# RELAY_8CH.net
KiCad netlist of a schematic drawn in Altium Designer
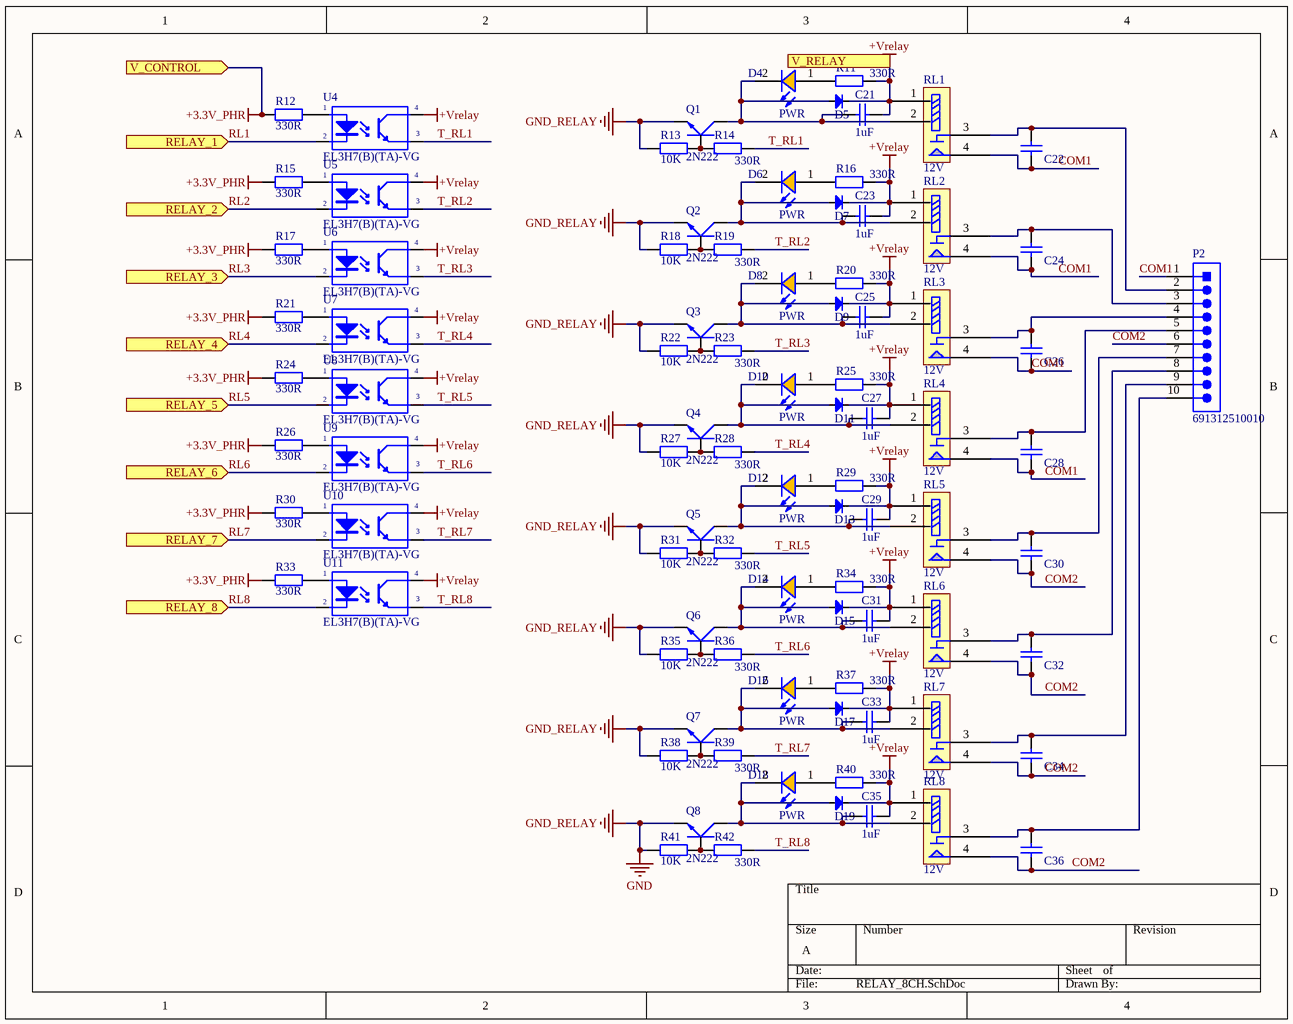
[diagram p0: RELAY_8CH.SchDoc]

(export (version "E")
  (design (tool "Eeschema 10.0.6"))
  (components
    (comp (ref "C21")
      (value "1uF")
      (footprint "CAP_0805")
      (description "WCAP-CSGP General Purpose Ceramic Capacitors")
      (fields (field (name "PART NUMBER") "885012005001") (field (name "PUBLISHER") "Wurth Elektronik"))
      (libsource (lib "ThanhNhan") (part "CAP_SMD"))
    )
    (comp (ref "C22")
      (value "R82DC3100DQ50J")
      (footprint "CAP FILM 5mm")
      (fields (field (name "MOUSER PART NUMBER") "80-R82DC3100DQ50J"))
      (libsource (lib "ThanhNhan") (part "CAP FILM"))
    )
    (comp (ref "C23")
      (value "1uF")
      (footprint "CAP_0805")
      (description "WCAP-CSGP General Purpose Ceramic Capacitors")
      (fields (field (name "PART NUMBER") "885012005001") (field (name "PUBLISHER") "Wurth Elektronik"))
      (libsource (lib "ThanhNhan") (part "CAP_SMD"))
    )
    (comp (ref "C24")
      (value "R82DC3100DQ50J")
      (footprint "CAP FILM 5mm")
      (fields (field (name "MOUSER PART NUMBER") "80-R82DC3100DQ50J"))
      (libsource (lib "ThanhNhan") (part "CAP FILM"))
    )
    (comp (ref "C25")
      (value "1uF")
      (footprint "CAP_0805")
      (description "WCAP-CSGP General Purpose Ceramic Capacitors")
      (fields (field (name "PART NUMBER") "885012005001") (field (name "PUBLISHER") "Wurth Elektronik"))
      (libsource (lib "ThanhNhan") (part "CAP_SMD"))
    )
    (comp (ref "C26")
      (value "R82DC3100DQ50J")
      (footprint "CAP FILM 5mm")
      (fields (field (name "MOUSER PART NUMBER") "80-R82DC3100DQ50J"))
      (libsource (lib "ThanhNhan") (part "CAP FILM"))
    )
    (comp (ref "C27")
      (value "1uF")
      (footprint "CAP_0805")
      (description "WCAP-CSGP General Purpose Ceramic Capacitors")
      (fields (field (name "PART NUMBER") "885012005001") (field (name "PUBLISHER") "Wurth Elektronik"))
      (libsource (lib "ThanhNhan") (part "CAP_SMD"))
    )
    (comp (ref "C28")
      (value "R82DC3100DQ50J")
      (footprint "CAP FILM 5mm")
      (fields (field (name "MOUSER PART NUMBER") "80-R82DC3100DQ50J"))
      (libsource (lib "ThanhNhan") (part "CAP FILM"))
    )
    (comp (ref "C29")
      (value "1uF")
      (footprint "CAP_0805")
      (description "WCAP-CSGP General Purpose Ceramic Capacitors")
      (fields (field (name "PART NUMBER") "885012005001") (field (name "PUBLISHER") "Wurth Elektronik"))
      (libsource (lib "ThanhNhan") (part "CAP_SMD"))
    )
    (comp (ref "C30")
      (value "R82DC3100DQ50J")
      (footprint "CAP FILM 5mm")
      (fields (field (name "MOUSER PART NUMBER") "80-R82DC3100DQ50J"))
      (libsource (lib "ThanhNhan") (part "CAP FILM"))
    )
    (comp (ref "C31")
      (value "1uF")
      (footprint "CAP_0805")
      (description "WCAP-CSGP General Purpose Ceramic Capacitors")
      (fields (field (name "PART NUMBER") "885012005001") (field (name "PUBLISHER") "Wurth Elektronik"))
      (libsource (lib "ThanhNhan") (part "CAP_SMD"))
    )
    (comp (ref "C32")
      (value "R82DC3100DQ50J")
      (footprint "CAP FILM 5mm")
      (fields (field (name "MOUSER PART NUMBER") "80-R82DC3100DQ50J"))
      (libsource (lib "ThanhNhan") (part "CAP FILM"))
    )
    (comp (ref "C33")
      (value "1uF")
      (footprint "CAP_0805")
      (description "WCAP-CSGP General Purpose Ceramic Capacitors")
      (fields (field (name "PART NUMBER") "885012005001") (field (name "PUBLISHER") "Wurth Elektronik"))
      (libsource (lib "ThanhNhan") (part "CAP_SMD"))
    )
    (comp (ref "C34")
      (value "R82DC3100DQ50J")
      (footprint "CAP FILM 5mm")
      (fields (field (name "MOUSER PART NUMBER") "80-R82DC3100DQ50J"))
      (libsource (lib "ThanhNhan") (part "CAP FILM"))
    )
    (comp (ref "C35")
      (value "1uF")
      (footprint "CAP_0805")
      (description "WCAP-CSGP General Purpose Ceramic Capacitors")
      (fields (field (name "PART NUMBER") "885012005001") (field (name "PUBLISHER") "Wurth Elektronik"))
      (libsource (lib "ThanhNhan") (part "CAP_SMD"))
    )
    (comp (ref "C36")
      (value "R82DC3100DQ50J")
      (footprint "CAP FILM 5mm")
      (fields (field (name "MOUSER PART NUMBER") "80-R82DC3100DQ50J"))
      (libsource (lib "ThanhNhan") (part "CAP FILM"))
    )
    (comp (ref "D4")
      (value "PWR")
      (footprint "WL-SMCW_0603_L1.6W0.8H0.7")
      (description "WL-SMCW SMT Mono-color Chip LED Waterclear, size 0603, Amber, 2V, 140°")
      (fields
        (field (name "MANUFACTURER") "Wurth Elektronik")
        (field (name "MANUFACTURER PART NUMBER") "150060AS75003")
      )
      (libsource (lib "Integrated_Library1") (part "150060AS75003"))
    )
    (comp (ref "D5")
      (value "Diode SMD")
      (footprint "DIO-SMD-106")
      (description "Default Diode")
      (fields (field (name "PUBLISHER") "Altium Limited"))
      (libsource (lib "Custom Library") (part "Diode SMD"))
    )
    (comp (ref "D6")
      (value "PWR")
      (footprint "WL-SMCW_0603_L1.6W0.8H0.7")
      (description "WL-SMCW SMT Mono-color Chip LED Waterclear, size 0603, Amber, 2V, 140°")
      (fields
        (field (name "MANUFACTURER") "Wurth Elektronik")
        (field (name "MANUFACTURER PART NUMBER") "150060AS75003")
      )
      (libsource (lib "Integrated_Library1") (part "150060AS75003"))
    )
    (comp (ref "D7")
      (value "Diode SMD")
      (footprint "DIO-SMD-106")
      (description "Default Diode")
      (fields (field (name "PUBLISHER") "Altium Limited"))
      (libsource (lib "Custom Library") (part "Diode SMD"))
    )
    (comp (ref "D8")
      (value "PWR")
      (footprint "WL-SMCW_0603_L1.6W0.8H0.7")
      (description "WL-SMCW SMT Mono-color Chip LED Waterclear, size 0603, Amber, 2V, 140°")
      (fields
        (field (name "MANUFACTURER") "Wurth Elektronik")
        (field (name "MANUFACTURER PART NUMBER") "150060AS75003")
      )
      (libsource (lib "Integrated_Library1") (part "150060AS75003"))
    )
    (comp (ref "D9")
      (value "Diode SMD")
      (footprint "DIO-SMD-106")
      (description "Default Diode")
      (fields (field (name "PUBLISHER") "Altium Limited"))
      (libsource (lib "Custom Library") (part "Diode SMD"))
    )
    (comp (ref "D10")
      (value "PWR")
      (footprint "WL-SMCW_0603_L1.6W0.8H0.7")
      (description "WL-SMCW SMT Mono-color Chip LED Waterclear, size 0603, Amber, 2V, 140°")
      (fields
        (field (name "MANUFACTURER") "Wurth Elektronik")
        (field (name "MANUFACTURER PART NUMBER") "150060AS75003")
      )
      (libsource (lib "Integrated_Library1") (part "150060AS75003"))
    )
    (comp (ref "D11")
      (value "Diode SMD")
      (footprint "DIO-SMD-106")
      (description "Default Diode")
      (fields (field (name "PUBLISHER") "Altium Limited"))
      (libsource (lib "Custom Library") (part "Diode SMD"))
    )
    (comp (ref "D12")
      (value "PWR")
      (footprint "WL-SMCW_0603_L1.6W0.8H0.7")
      (description "WL-SMCW SMT Mono-color Chip LED Waterclear, size 0603, Amber, 2V, 140°")
      (fields
        (field (name "MANUFACTURER") "Wurth Elektronik")
        (field (name "MANUFACTURER PART NUMBER") "150060AS75003")
      )
      (libsource (lib "Integrated_Library1") (part "150060AS75003"))
    )
    (comp (ref "D13")
      (value "Diode SMD")
      (footprint "DIO-SMD-106")
      (description "Default Diode")
      (fields (field (name "PUBLISHER") "Altium Limited"))
      (libsource (lib "Custom Library") (part "Diode SMD"))
    )
    (comp (ref "D14")
      (value "PWR")
      (footprint "WL-SMCW_0603_L1.6W0.8H0.7")
      (description "WL-SMCW SMT Mono-color Chip LED Waterclear, size 0603, Amber, 2V, 140°")
      (fields
        (field (name "MANUFACTURER") "Wurth Elektronik")
        (field (name "MANUFACTURER PART NUMBER") "150060AS75003")
      )
      (libsource (lib "Integrated_Library1") (part "150060AS75003"))
    )
    (comp (ref "D15")
      (value "Diode SMD")
      (footprint "DIO-SMD-106")
      (description "Default Diode")
      (fields (field (name "PUBLISHER") "Altium Limited"))
      (libsource (lib "Custom Library") (part "Diode SMD"))
    )
    (comp (ref "D16")
      (value "PWR")
      (footprint "WL-SMCW_0603_L1.6W0.8H0.7")
      (description "WL-SMCW SMT Mono-color Chip LED Waterclear, size 0603, Amber, 2V, 140°")
      (fields
        (field (name "MANUFACTURER") "Wurth Elektronik")
        (field (name "MANUFACTURER PART NUMBER") "150060AS75003")
      )
      (libsource (lib "Integrated_Library1") (part "150060AS75003"))
    )
    (comp (ref "D17")
      (value "Diode SMD")
      (footprint "DIO-SMD-106")
      (description "Default Diode")
      (fields (field (name "PUBLISHER") "Altium Limited"))
      (libsource (lib "Custom Library") (part "Diode SMD"))
    )
    (comp (ref "D18")
      (value "PWR")
      (footprint "WL-SMCW_0603_L1.6W0.8H0.7")
      (description "WL-SMCW SMT Mono-color Chip LED Waterclear, size 0603, Amber, 2V, 140°")
      (fields
        (field (name "MANUFACTURER") "Wurth Elektronik")
        (field (name "MANUFACTURER PART NUMBER") "150060AS75003")
      )
      (libsource (lib "Integrated_Library1") (part "150060AS75003"))
    )
    (comp (ref "D19")
      (value "Diode SMD")
      (footprint "DIO-SMD-106")
      (description "Default Diode")
      (fields (field (name "PUBLISHER") "Altium Limited"))
      (libsource (lib "Custom Library") (part "Diode SMD"))
    )
    (comp (ref "P2")
      (value "691312510010")
      (footprint "691312510010")
      (description "WR-TBL Serie 312 Open Horizontal PCB Header, Pluggable, THT, pitch 5.08mm, 10p")
      (fields (field (name "MANUFACTURER") "Wurth Elektronik"))
      (libsource (lib "Integrated_Library1") (part "691312510010"))
    )
    (comp (ref "Q1")
      (value "2N222")
      (footprint "SOT23-231")
      (description "NPN 600mW, ECB")
      (libsource (lib "Custom Library") (part "2N222"))
    )
    (comp (ref "Q2")
      (value "2N222")
      (footprint "SOT23-231")
      (description "NPN 600mW, ECB")
      (libsource (lib "Custom Library") (part "2N222"))
    )
    (comp (ref "Q3")
      (value "2N222")
      (footprint "SOT23-231")
      (description "NPN 600mW, ECB")
      (libsource (lib "Custom Library") (part "2N222"))
    )
    (comp (ref "Q4")
      (value "2N222")
      (footprint "SOT23-231")
      (description "NPN 600mW, ECB")
      (libsource (lib "Custom Library") (part "2N222"))
    )
    (comp (ref "Q5")
      (value "2N222")
      (footprint "SOT23-231")
      (description "NPN 600mW, ECB")
      (libsource (lib "Custom Library") (part "2N222"))
    )
    (comp (ref "Q6")
      (value "2N222")
      (footprint "SOT23-231")
      (description "NPN 600mW, ECB")
      (libsource (lib "Custom Library") (part "2N222"))
    )
    (comp (ref "Q7")
      (value "2N222")
      (footprint "SOT23-231")
      (description "NPN 600mW, ECB")
      (libsource (lib "Custom Library") (part "2N222"))
    )
    (comp (ref "Q8")
      (value "2N222")
      (footprint "SOT23-231")
      (description "NPN 600mW, ECB")
      (libsource (lib "Custom Library") (part "2N222"))
    )
    (comp (ref "R11")
      (value "330R")
      (footprint "RES_0603")
      (description "WRIS-KSKE SMT Thick Film Resistor, 0.125W")
      (fields
        (field (name "MANUFACTURER") "Wurth Elektronik")
        (field (name "MANUFACTURER PART NUMBER") "560050310010")
      )
      (libsource (lib "") (part "RES_SMD_1"))
    )
    (comp (ref "R12")
      (value "330R")
      (footprint "RES_0603")
      (description "WRIS-KSKE SMT Thick Film Resistor, 0.125W")
      (fields
        (field (name "MANUFACTURER") "Wurth Elektronik")
        (field (name "MANUFACTURER PART NUMBER") "560050310010")
      )
      (libsource (lib "ThanhNhan") (part "RES_SMD"))
    )
    (comp (ref "R13")
      (value "10K")
      (footprint "RES_0603")
      (description "WRIS-KSKE SMT Thick Film Resistor, 0.125W")
      (fields
        (field (name "MANUFACTURER") "Wurth Elektronik")
        (field (name "MANUFACTURER PART NUMBER") "560050310010")
      )
      (libsource (lib "ThanhNhan") (part "RES_SMD"))
    )
    (comp (ref "R14")
      (value "330R")
      (footprint "RES_0603")
      (description "WRIS-KSKE SMT Thick Film Resistor, 0.125W")
      (fields
        (field (name "MANUFACTURER") "Wurth Elektronik")
        (field (name "MANUFACTURER PART NUMBER") "560050310010")
      )
      (libsource (lib "ThanhNhan") (part "RES_SMD"))
    )
    (comp (ref "R15")
      (value "330R")
      (footprint "RES_0603")
      (description "WRIS-KSKE SMT Thick Film Resistor, 0.125W")
      (fields
        (field (name "MANUFACTURER") "Wurth Elektronik")
        (field (name "MANUFACTURER PART NUMBER") "560050310010")
      )
      (libsource (lib "ThanhNhan") (part "RES_SMD"))
    )
    (comp (ref "R16")
      (value "330R")
      (footprint "RES_0603")
      (description "WRIS-KSKE SMT Thick Film Resistor, 0.125W")
      (fields
        (field (name "MANUFACTURER") "Wurth Elektronik")
        (field (name "MANUFACTURER PART NUMBER") "560050310010")
      )
      (libsource (lib "") (part "RES_SMD_1"))
    )
    (comp (ref "R17")
      (value "330R")
      (footprint "RES_0603")
      (description "WRIS-KSKE SMT Thick Film Resistor, 0.125W")
      (fields
        (field (name "MANUFACTURER") "Wurth Elektronik")
        (field (name "MANUFACTURER PART NUMBER") "560050310010")
      )
      (libsource (lib "ThanhNhan") (part "RES_SMD"))
    )
    (comp (ref "R18")
      (value "10K")
      (footprint "RES_0603")
      (description "WRIS-KSKE SMT Thick Film Resistor, 0.125W")
      (fields
        (field (name "MANUFACTURER") "Wurth Elektronik")
        (field (name "MANUFACTURER PART NUMBER") "560050310010")
      )
      (libsource (lib "ThanhNhan") (part "RES_SMD"))
    )
    (comp (ref "R19")
      (value "330R")
      (footprint "RES_0603")
      (description "WRIS-KSKE SMT Thick Film Resistor, 0.125W")
      (fields
        (field (name "MANUFACTURER") "Wurth Elektronik")
        (field (name "MANUFACTURER PART NUMBER") "560050310010")
      )
      (libsource (lib "ThanhNhan") (part "RES_SMD"))
    )
    (comp (ref "R20")
      (value "330R")
      (footprint "RES_0603")
      (description "WRIS-KSKE SMT Thick Film Resistor, 0.125W")
      (fields
        (field (name "MANUFACTURER") "Wurth Elektronik")
        (field (name "MANUFACTURER PART NUMBER") "560050310010")
      )
      (libsource (lib "") (part "RES_SMD_1"))
    )
    (comp (ref "R21")
      (value "330R")
      (footprint "RES_0603")
      (description "WRIS-KSKE SMT Thick Film Resistor, 0.125W")
      (fields
        (field (name "MANUFACTURER") "Wurth Elektronik")
        (field (name "MANUFACTURER PART NUMBER") "560050310010")
      )
      (libsource (lib "ThanhNhan") (part "RES_SMD"))
    )
    (comp (ref "R22")
      (value "10K")
      (footprint "RES_0603")
      (description "WRIS-KSKE SMT Thick Film Resistor, 0.125W")
      (fields
        (field (name "MANUFACTURER") "Wurth Elektronik")
        (field (name "MANUFACTURER PART NUMBER") "560050310010")
      )
      (libsource (lib "ThanhNhan") (part "RES_SMD"))
    )
    (comp (ref "R23")
      (value "330R")
      (footprint "RES_0603")
      (description "WRIS-KSKE SMT Thick Film Resistor, 0.125W")
      (fields
        (field (name "MANUFACTURER") "Wurth Elektronik")
        (field (name "MANUFACTURER PART NUMBER") "560050310010")
      )
      (libsource (lib "ThanhNhan") (part "RES_SMD"))
    )
    (comp (ref "R24")
      (value "330R")
      (footprint "RES_0603")
      (description "WRIS-KSKE SMT Thick Film Resistor, 0.125W")
      (fields
        (field (name "MANUFACTURER") "Wurth Elektronik")
        (field (name "MANUFACTURER PART NUMBER") "560050310010")
      )
      (libsource (lib "ThanhNhan") (part "RES_SMD"))
    )
    (comp (ref "R25")
      (value "330R")
      (footprint "RES_0603")
      (description "WRIS-KSKE SMT Thick Film Resistor, 0.125W")
      (fields
        (field (name "MANUFACTURER") "Wurth Elektronik")
        (field (name "MANUFACTURER PART NUMBER") "560050310010")
      )
      (libsource (lib "") (part "RES_SMD_1"))
    )
    (comp (ref "R26")
      (value "330R")
      (footprint "RES_0603")
      (description "WRIS-KSKE SMT Thick Film Resistor, 0.125W")
      (fields
        (field (name "MANUFACTURER") "Wurth Elektronik")
        (field (name "MANUFACTURER PART NUMBER") "560050310010")
      )
      (libsource (lib "ThanhNhan") (part "RES_SMD"))
    )
    (comp (ref "R27")
      (value "10K")
      (footprint "RES_0603")
      (description "WRIS-KSKE SMT Thick Film Resistor, 0.125W")
      (fields
        (field (name "MANUFACTURER") "Wurth Elektronik")
        (field (name "MANUFACTURER PART NUMBER") "560050310010")
      )
      (libsource (lib "ThanhNhan") (part "RES_SMD"))
    )
    (comp (ref "R28")
      (value "330R")
      (footprint "RES_0603")
      (description "WRIS-KSKE SMT Thick Film Resistor, 0.125W")
      (fields
        (field (name "MANUFACTURER") "Wurth Elektronik")
        (field (name "MANUFACTURER PART NUMBER") "560050310010")
      )
      (libsource (lib "ThanhNhan") (part "RES_SMD"))
    )
    (comp (ref "R29")
      (value "330R")
      (footprint "RES_0603")
      (description "WRIS-KSKE SMT Thick Film Resistor, 0.125W")
      (fields
        (field (name "MANUFACTURER") "Wurth Elektronik")
        (field (name "MANUFACTURER PART NUMBER") "560050310010")
      )
      (libsource (lib "") (part "RES_SMD_1"))
    )
    (comp (ref "R30")
      (value "330R")
      (footprint "RES_0603")
      (description "WRIS-KSKE SMT Thick Film Resistor, 0.125W")
      (fields
        (field (name "MANUFACTURER") "Wurth Elektronik")
        (field (name "MANUFACTURER PART NUMBER") "560050310010")
      )
      (libsource (lib "ThanhNhan") (part "RES_SMD"))
    )
    (comp (ref "R31")
      (value "10K")
      (footprint "RES_0603")
      (description "WRIS-KSKE SMT Thick Film Resistor, 0.125W")
      (fields
        (field (name "MANUFACTURER") "Wurth Elektronik")
        (field (name "MANUFACTURER PART NUMBER") "560050310010")
      )
      (libsource (lib "ThanhNhan") (part "RES_SMD"))
    )
    (comp (ref "R32")
      (value "330R")
      (footprint "RES_0603")
      (description "WRIS-KSKE SMT Thick Film Resistor, 0.125W")
      (fields
        (field (name "MANUFACTURER") "Wurth Elektronik")
        (field (name "MANUFACTURER PART NUMBER") "560050310010")
      )
      (libsource (lib "ThanhNhan") (part "RES_SMD"))
    )
    (comp (ref "R33")
      (value "330R")
      (footprint "RES_0603")
      (description "WRIS-KSKE SMT Thick Film Resistor, 0.125W")
      (fields
        (field (name "MANUFACTURER") "Wurth Elektronik")
        (field (name "MANUFACTURER PART NUMBER") "560050310010")
      )
      (libsource (lib "ThanhNhan") (part "RES_SMD"))
    )
    (comp (ref "R34")
      (value "330R")
      (footprint "RES_0603")
      (description "WRIS-KSKE SMT Thick Film Resistor, 0.125W")
      (fields
        (field (name "MANUFACTURER") "Wurth Elektronik")
        (field (name "MANUFACTURER PART NUMBER") "560050310010")
      )
      (libsource (lib "") (part "RES_SMD_1"))
    )
    (comp (ref "R35")
      (value "10K")
      (footprint "RES_0603")
      (description "WRIS-KSKE SMT Thick Film Resistor, 0.125W")
      (fields
        (field (name "MANUFACTURER") "Wurth Elektronik")
        (field (name "MANUFACTURER PART NUMBER") "560050310010")
      )
      (libsource (lib "ThanhNhan") (part "RES_SMD"))
    )
    (comp (ref "R36")
      (value "330R")
      (footprint "RES_0603")
      (description "WRIS-KSKE SMT Thick Film Resistor, 0.125W")
      (fields
        (field (name "MANUFACTURER") "Wurth Elektronik")
        (field (name "MANUFACTURER PART NUMBER") "560050310010")
      )
      (libsource (lib "ThanhNhan") (part "RES_SMD"))
    )
    (comp (ref "R37")
      (value "330R")
      (footprint "RES_0603")
      (description "WRIS-KSKE SMT Thick Film Resistor, 0.125W")
      (fields
        (field (name "MANUFACTURER") "Wurth Elektronik")
        (field (name "MANUFACTURER PART NUMBER") "560050310010")
      )
      (libsource (lib "") (part "RES_SMD_1"))
    )
    (comp (ref "R38")
      (value "10K")
      (footprint "RES_0603")
      (description "WRIS-KSKE SMT Thick Film Resistor, 0.125W")
      (fields
        (field (name "MANUFACTURER") "Wurth Elektronik")
        (field (name "MANUFACTURER PART NUMBER") "560050310010")
      )
      (libsource (lib "ThanhNhan") (part "RES_SMD"))
    )
    (comp (ref "R39")
      (value "330R")
      (footprint "RES_0603")
      (description "WRIS-KSKE SMT Thick Film Resistor, 0.125W")
      (fields
        (field (name "MANUFACTURER") "Wurth Elektronik")
        (field (name "MANUFACTURER PART NUMBER") "560050310010")
      )
      (libsource (lib "ThanhNhan") (part "RES_SMD"))
    )
    (comp (ref "R40")
      (value "330R")
      (footprint "RES_0603")
      (description "WRIS-KSKE SMT Thick Film Resistor, 0.125W")
      (fields
        (field (name "MANUFACTURER") "Wurth Elektronik")
        (field (name "MANUFACTURER PART NUMBER") "560050310010")
      )
      (libsource (lib "") (part "RES_SMD_1"))
    )
    (comp (ref "R41")
      (value "10K")
      (footprint "RES_0603")
      (description "WRIS-KSKE SMT Thick Film Resistor, 0.125W")
      (fields
        (field (name "MANUFACTURER") "Wurth Elektronik")
        (field (name "MANUFACTURER PART NUMBER") "560050310010")
      )
      (libsource (lib "ThanhNhan") (part "RES_SMD"))
    )
    (comp (ref "R42")
      (value "330R")
      (footprint "RES_0603")
      (description "WRIS-KSKE SMT Thick Film Resistor, 0.125W")
      (fields
        (field (name "MANUFACTURER") "Wurth Elektronik")
        (field (name "MANUFACTURER PART NUMBER") "560050310010")
      )
      (libsource (lib "ThanhNhan") (part "RES_SMD"))
    )
    (comp (ref "RL1")
      (value "12V")
      (footprint "HF46F")
      (description "Relay 5V HF46F")
      (libsource (lib "ThanhNhan") (part "HONGFA HF46F"))
    )
    (comp (ref "RL2")
      (value "12V")
      (footprint "HF46F")
      (description "Relay 5V HF46F")
      (libsource (lib "ThanhNhan") (part "HONGFA HF46F"))
    )
    (comp (ref "RL3")
      (value "12V")
      (footprint "HF46F")
      (description "Relay 5V HF46F")
      (libsource (lib "ThanhNhan") (part "HONGFA HF46F"))
    )
    (comp (ref "RL4")
      (value "12V")
      (footprint "HF46F")
      (description "Relay 5V HF46F")
      (libsource (lib "ThanhNhan") (part "HONGFA HF46F"))
    )
    (comp (ref "RL5")
      (value "12V")
      (footprint "HF46F")
      (description "Relay 5V HF46F")
      (libsource (lib "ThanhNhan") (part "HONGFA HF46F"))
    )
    (comp (ref "RL6")
      (value "12V")
      (footprint "HF46F")
      (description "Relay 5V HF46F")
      (libsource (lib "ThanhNhan") (part "HONGFA HF46F"))
    )
    (comp (ref "RL7")
      (value "12V")
      (footprint "HF46F")
      (description "Relay 5V HF46F")
      (libsource (lib "ThanhNhan") (part "HONGFA HF46F"))
    )
    (comp (ref "RL8")
      (value "12V")
      (footprint "HF46F")
      (description "Relay 5V HF46F")
      (libsource (lib "ThanhNhan") (part "HONGFA HF46F"))
    )
    (comp (ref "U4")
      (value "UNK_Everlight_EL3H7_B_TA_-VG_eec")
      (footprint "Everlight_EL3H7_B_TA_-VG_0")
      (description "UNK OPTOISOLATOR 3.75KV TRANS 4-SSOP")
      (fields
        (field (name "MANUFACTURER") "Everlight")
        (field (name "MOUSER PART NUMBER") "638-EL3H7BTAVG")
        (field (name "PART NUMBER") "EL3H7(B)(TA)-VG")
      )
      (libsource (lib "myAltium") (part "UNK_Everlight_EL3H7_B_TA_-VG_eec"))
    )
    (comp (ref "U5")
      (value "UNK_Everlight_EL3H7_B_TA_-VG_eec")
      (footprint "Everlight_EL3H7_B_TA_-VG_0")
      (description "UNK OPTOISOLATOR 3.75KV TRANS 4-SSOP")
      (fields
        (field (name "MANUFACTURER") "Everlight")
        (field (name "MOUSER PART NUMBER") "638-EL3H7BTAVG")
        (field (name "PART NUMBER") "EL3H7(B)(TA)-VG")
      )
      (libsource (lib "myAltium") (part "UNK_Everlight_EL3H7_B_TA_-VG_eec"))
    )
    (comp (ref "U6")
      (value "UNK_Everlight_EL3H7_B_TA_-VG_eec")
      (footprint "Everlight_EL3H7_B_TA_-VG_0")
      (description "UNK OPTOISOLATOR 3.75KV TRANS 4-SSOP")
      (fields
        (field (name "MANUFACTURER") "Everlight")
        (field (name "MOUSER PART NUMBER") "638-EL3H7BTAVG")
        (field (name "PART NUMBER") "EL3H7(B)(TA)-VG")
      )
      (libsource (lib "myAltium") (part "UNK_Everlight_EL3H7_B_TA_-VG_eec"))
    )
    (comp (ref "U7")
      (value "UNK_Everlight_EL3H7_B_TA_-VG_eec")
      (footprint "Everlight_EL3H7_B_TA_-VG_0")
      (description "UNK OPTOISOLATOR 3.75KV TRANS 4-SSOP")
      (fields
        (field (name "MANUFACTURER") "Everlight")
        (field (name "MOUSER PART NUMBER") "638-EL3H7BTAVG")
        (field (name "PART NUMBER") "EL3H7(B)(TA)-VG")
      )
      (libsource (lib "myAltium") (part "UNK_Everlight_EL3H7_B_TA_-VG_eec"))
    )
    (comp (ref "U8")
      (value "UNK_Everlight_EL3H7_B_TA_-VG_eec")
      (footprint "Everlight_EL3H7_B_TA_-VG_0")
      (description "UNK OPTOISOLATOR 3.75KV TRANS 4-SSOP")
      (fields
        (field (name "MANUFACTURER") "Everlight")
        (field (name "MOUSER PART NUMBER") "638-EL3H7BTAVG")
        (field (name "PART NUMBER") "EL3H7(B)(TA)-VG")
      )
      (libsource (lib "myAltium") (part "UNK_Everlight_EL3H7_B_TA_-VG_eec"))
    )
    (comp (ref "U9")
      (value "UNK_Everlight_EL3H7_B_TA_-VG_eec")
      (footprint "Everlight_EL3H7_B_TA_-VG_0")
      (description "UNK OPTOISOLATOR 3.75KV TRANS 4-SSOP")
      (fields
        (field (name "MANUFACTURER") "Everlight")
        (field (name "MOUSER PART NUMBER") "638-EL3H7BTAVG")
        (field (name "PART NUMBER") "EL3H7(B)(TA)-VG")
      )
      (libsource (lib "myAltium") (part "UNK_Everlight_EL3H7_B_TA_-VG_eec"))
    )
    (comp (ref "U10")
      (value "UNK_Everlight_EL3H7_B_TA_-VG_eec")
      (footprint "Everlight_EL3H7_B_TA_-VG_0")
      (description "UNK OPTOISOLATOR 3.75KV TRANS 4-SSOP")
      (fields
        (field (name "MANUFACTURER") "Everlight")
        (field (name "MOUSER PART NUMBER") "638-EL3H7BTAVG")
        (field (name "PART NUMBER") "EL3H7(B)(TA)-VG")
      )
      (libsource (lib "myAltium") (part "UNK_Everlight_EL3H7_B_TA_-VG_eec"))
    )
    (comp (ref "U11")
      (value "UNK_Everlight_EL3H7_B_TA_-VG_eec")
      (footprint "Everlight_EL3H7_B_TA_-VG_0")
      (description "UNK OPTOISOLATOR 3.75KV TRANS 4-SSOP")
      (fields
        (field (name "MANUFACTURER") "Everlight")
        (field (name "MOUSER PART NUMBER") "638-EL3H7BTAVG")
        (field (name "PART NUMBER") "EL3H7(B)(TA)-VG")
      )
      (libsource (lib "myAltium") (part "UNK_Everlight_EL3H7_B_TA_-VG_eec"))
    )
  )
  (nets
    (net (code "1") (name "+3.3V_PHR") (class "Default")
      (node (ref "R12") (pin "1") (pinfunction "1_1") (pintype "passive"))
      (node (ref "R15") (pin "1") (pinfunction "1_1") (pintype "passive"))
      (node (ref "R17") (pin "1") (pinfunction "1_1") (pintype "passive"))
      (node (ref "R21") (pin "1") (pinfunction "1_1") (pintype "passive"))
      (node (ref "R24") (pin "1") (pinfunction "1_1") (pintype "passive"))
      (node (ref "R26") (pin "1") (pinfunction "1_1") (pintype "passive"))
      (node (ref "R30") (pin "1") (pinfunction "1_1") (pintype "passive"))
      (node (ref "R33") (pin "1") (pinfunction "1_1") (pintype "passive"))
    )
    (net (code "2") (name "+Vrelay") (class "Default")
      (node (ref "C21") (pin "1") (pinfunction "1_1") (pintype "passive"))
      (node (ref "C23") (pin "1") (pinfunction "1_1") (pintype "passive"))
      (node (ref "C25") (pin "1") (pinfunction "1_1") (pintype "passive"))
      (node (ref "C27") (pin "1") (pinfunction "1_1") (pintype "passive"))
      (node (ref "C29") (pin "1") (pinfunction "1_1") (pintype "passive"))
      (node (ref "C31") (pin "1") (pinfunction "1_1") (pintype "passive"))
      (node (ref "C33") (pin "1") (pinfunction "1_1") (pintype "passive"))
      (node (ref "C35") (pin "1") (pinfunction "1_1") (pintype "passive"))
      (node (ref "D11") (pin "2") (pinfunction "K_2") (pintype "passive"))
      (node (ref "D13") (pin "2") (pinfunction "K_2") (pintype "passive"))
      (node (ref "D15") (pin "2") (pinfunction "K_2") (pintype "passive"))
      (node (ref "D17") (pin "2") (pinfunction "K_2") (pintype "passive"))
      (node (ref "D19") (pin "2") (pinfunction "K_2") (pintype "passive"))
      (node (ref "D5") (pin "2") (pinfunction "K_2") (pintype "passive"))
      (node (ref "D7") (pin "2") (pinfunction "K_2") (pintype "passive"))
      (node (ref "D9") (pin "2") (pinfunction "K_2") (pintype "passive"))
      (node (ref "R11") (pin "1") (pinfunction "1_1") (pintype "passive"))
      (node (ref "R16") (pin "1") (pinfunction "1_1") (pintype "passive"))
      (node (ref "R20") (pin "1") (pinfunction "1_1") (pintype "passive"))
      (node (ref "R25") (pin "1") (pinfunction "1_1") (pintype "passive"))
      (node (ref "R29") (pin "1") (pinfunction "1_1") (pintype "passive"))
      (node (ref "R34") (pin "1") (pinfunction "1_1") (pintype "passive"))
      (node (ref "R37") (pin "1") (pinfunction "1_1") (pintype "passive"))
      (node (ref "R40") (pin "1") (pinfunction "1_1") (pintype "passive"))
      (node (ref "RL1") (pin "1") (pinfunction "9_1") (pintype "passive"))
      (node (ref "RL2") (pin "1") (pinfunction "9_1") (pintype "passive"))
      (node (ref "RL3") (pin "1") (pinfunction "9_1") (pintype "passive"))
      (node (ref "RL4") (pin "1") (pinfunction "9_1") (pintype "passive"))
      (node (ref "RL5") (pin "1") (pinfunction "9_1") (pintype "passive"))
      (node (ref "RL6") (pin "1") (pinfunction "9_1") (pintype "passive"))
      (node (ref "RL7") (pin "1") (pinfunction "9_1") (pintype "passive"))
      (node (ref "RL8") (pin "1") (pinfunction "9_1") (pintype "passive"))
      (node (ref "U10") (pin "4") (pinfunction "C_4") (pintype "passive"))
      (node (ref "U11") (pin "4") (pinfunction "C_4") (pintype "passive"))
      (node (ref "U4") (pin "4") (pinfunction "C_4") (pintype "passive"))
      (node (ref "U5") (pin "4") (pinfunction "C_4") (pintype "passive"))
      (node (ref "U6") (pin "4") (pinfunction "C_4") (pintype "passive"))
      (node (ref "U7") (pin "4") (pinfunction "C_4") (pintype "passive"))
      (node (ref "U8") (pin "4") (pinfunction "C_4") (pintype "passive"))
      (node (ref "U9") (pin "4") (pinfunction "C_4") (pintype "passive"))
    )
    (net (code "3") (name "/COM1") (class "Default")
      (node (ref "C22") (pin "2") (pinfunction "2_2") (pintype "passive"))
      (node (ref "C24") (pin "2") (pinfunction "2_2") (pintype "passive"))
      (node (ref "C26") (pin "2") (pinfunction "2_2") (pintype "passive"))
      (node (ref "C28") (pin "2") (pinfunction "2_2") (pintype "passive"))
      (node (ref "P2") (pin "1") (pinfunction "1_1") (pintype "passive"))
      (node (ref "RL1") (pin "4") (pinfunction "10_4") (pintype "passive"))
      (node (ref "RL2") (pin "4") (pinfunction "10_4") (pintype "passive"))
      (node (ref "RL3") (pin "4") (pinfunction "10_4") (pintype "passive"))
      (node (ref "RL4") (pin "4") (pinfunction "10_4") (pintype "passive"))
    )
    (net (code "4") (name "/COM2") (class "Default")
      (node (ref "C30") (pin "2") (pinfunction "2_2") (pintype "passive"))
      (node (ref "C32") (pin "2") (pinfunction "2_2") (pintype "passive"))
      (node (ref "C34") (pin "2") (pinfunction "2_2") (pintype "passive"))
      (node (ref "C36") (pin "2") (pinfunction "2_2") (pintype "passive"))
      (node (ref "P2") (pin "6") (pinfunction "6_6") (pintype "passive"))
      (node (ref "RL5") (pin "4") (pinfunction "10_4") (pintype "passive"))
      (node (ref "RL6") (pin "4") (pinfunction "10_4") (pintype "passive"))
      (node (ref "RL7") (pin "4") (pinfunction "10_4") (pintype "passive"))
      (node (ref "RL8") (pin "4") (pinfunction "10_4") (pintype "passive"))
    )
    (net (code "5") (name "/RL1") (class "Default")
      (node (ref "U4") (pin "2") (pinfunction "K_2") (pintype "passive"))
    )
    (net (code "6") (name "/RL2") (class "Default")
      (node (ref "U5") (pin "2") (pinfunction "K_2") (pintype "passive"))
    )
    (net (code "7") (name "/RL3") (class "Default")
      (node (ref "U6") (pin "2") (pinfunction "K_2") (pintype "passive"))
    )
    (net (code "8") (name "/RL4") (class "Default")
      (node (ref "U7") (pin "2") (pinfunction "K_2") (pintype "passive"))
    )
    (net (code "9") (name "/RL5") (class "Default")
      (node (ref "U8") (pin "2") (pinfunction "K_2") (pintype "passive"))
    )
    (net (code "10") (name "/RL6") (class "Default")
      (node (ref "U9") (pin "2") (pinfunction "K_2") (pintype "passive"))
    )
    (net (code "11") (name "/RL7") (class "Default")
      (node (ref "U10") (pin "2") (pinfunction "K_2") (pintype "passive"))
    )
    (net (code "12") (name "/RL8") (class "Default")
      (node (ref "U11") (pin "2") (pinfunction "K_2") (pintype "passive"))
    )
    (net (code "13") (name "/T_RL1") (class "Default")
      (node (ref "R14") (pin "2") (pinfunction "2_2") (pintype "passive"))
      (node (ref "U4") (pin "3") (pinfunction "E_3") (pintype "passive"))
    )
    (net (code "14") (name "/T_RL2") (class "Default")
      (node (ref "R19") (pin "2") (pinfunction "2_2") (pintype "passive"))
      (node (ref "U5") (pin "3") (pinfunction "E_3") (pintype "passive"))
    )
    (net (code "15") (name "/T_RL3") (class "Default")
      (node (ref "R23") (pin "2") (pinfunction "2_2") (pintype "passive"))
      (node (ref "U6") (pin "3") (pinfunction "E_3") (pintype "passive"))
    )
    (net (code "16") (name "/T_RL4") (class "Default")
      (node (ref "R28") (pin "2") (pinfunction "2_2") (pintype "passive"))
      (node (ref "U7") (pin "3") (pinfunction "E_3") (pintype "passive"))
    )
    (net (code "17") (name "/T_RL5") (class "Default")
      (node (ref "R32") (pin "2") (pinfunction "2_2") (pintype "passive"))
      (node (ref "U8") (pin "3") (pinfunction "E_3") (pintype "passive"))
    )
    (net (code "18") (name "/T_RL6") (class "Default")
      (node (ref "R36") (pin "2") (pinfunction "2_2") (pintype "passive"))
      (node (ref "U9") (pin "3") (pinfunction "E_3") (pintype "passive"))
    )
    (net (code "19") (name "/T_RL7") (class "Default")
      (node (ref "R39") (pin "2") (pinfunction "2_2") (pintype "passive"))
      (node (ref "U10") (pin "3") (pinfunction "E_3") (pintype "passive"))
    )
    (net (code "20") (name "/T_RL8") (class "Default")
      (node (ref "R42") (pin "2") (pinfunction "2_2") (pintype "passive"))
      (node (ref "U11") (pin "3") (pinfunction "E_3") (pintype "passive"))
    )
    (net (code "22") (name "GND") (class "Default")
      (node (ref "Q1") (pin "1") (pinfunction "E_1") (pintype "passive"))
      (node (ref "Q2") (pin "1") (pinfunction "E_1") (pintype "passive"))
      (node (ref "Q3") (pin "1") (pinfunction "E_1") (pintype "passive"))
      (node (ref "Q4") (pin "1") (pinfunction "E_1") (pintype "passive"))
      (node (ref "Q5") (pin "1") (pinfunction "E_1") (pintype "passive"))
      (node (ref "Q6") (pin "1") (pinfunction "E_1") (pintype "passive"))
      (node (ref "Q7") (pin "1") (pinfunction "E_1") (pintype "passive"))
      (node (ref "Q8") (pin "1") (pinfunction "E_1") (pintype "passive"))
      (node (ref "R13") (pin "1") (pinfunction "1_1") (pintype "passive"))
      (node (ref "R18") (pin "1") (pinfunction "1_1") (pintype "passive"))
      (node (ref "R22") (pin "1") (pinfunction "1_1") (pintype "passive"))
      (node (ref "R27") (pin "1") (pinfunction "1_1") (pintype "passive"))
      (node (ref "R31") (pin "1") (pinfunction "1_1") (pintype "passive"))
      (node (ref "R35") (pin "1") (pinfunction "1_1") (pintype "passive"))
      (node (ref "R38") (pin "1") (pinfunction "1_1") (pintype "passive"))
      (node (ref "R41") (pin "1") (pinfunction "1_1") (pintype "passive"))
    )
    (net (code "23") (name "Net-(D4-A)") (class "Default")
      (node (ref "D4") (pin "1") (pinfunction "A_1") (pintype "passive"))
      (node (ref "R11") (pin "2") (pinfunction "2_2") (pintype "passive"))
    )
    (net (code "24") (name "Net-(D4-K)") (class "Default")
      (node (ref "C21") (pin "2") (pinfunction "2_2") (pintype "passive"))
      (node (ref "D4") (pin "2") (pinfunction "K_2") (pintype "passive"))
      (node (ref "D5") (pin "1") (pinfunction "A_1") (pintype "passive"))
      (node (ref "Q1") (pin "3") (pinfunction "C_3") (pintype "passive"))
      (node (ref "RL1") (pin "2") (pinfunction "9_2") (pintype "passive"))
    )
    (net (code "25") (name "Net-(D6-A)") (class "Default")
      (node (ref "D6") (pin "1") (pinfunction "A_1") (pintype "passive"))
      (node (ref "R16") (pin "2") (pinfunction "2_2") (pintype "passive"))
    )
    (net (code "26") (name "Net-(D6-K)") (class "Default")
      (node (ref "C23") (pin "2") (pinfunction "2_2") (pintype "passive"))
      (node (ref "D6") (pin "2") (pinfunction "K_2") (pintype "passive"))
      (node (ref "D7") (pin "1") (pinfunction "A_1") (pintype "passive"))
      (node (ref "Q2") (pin "3") (pinfunction "C_3") (pintype "passive"))
      (node (ref "RL2") (pin "2") (pinfunction "9_2") (pintype "passive"))
    )
    (net (code "27") (name "Net-(D8-A)") (class "Default")
      (node (ref "D8") (pin "1") (pinfunction "A_1") (pintype "passive"))
      (node (ref "R20") (pin "2") (pinfunction "2_2") (pintype "passive"))
    )
    (net (code "28") (name "Net-(D8-K)") (class "Default")
      (node (ref "C25") (pin "2") (pinfunction "2_2") (pintype "passive"))
      (node (ref "D8") (pin "2") (pinfunction "K_2") (pintype "passive"))
      (node (ref "D9") (pin "1") (pinfunction "A_1") (pintype "passive"))
      (node (ref "Q3") (pin "3") (pinfunction "C_3") (pintype "passive"))
      (node (ref "RL3") (pin "2") (pinfunction "9_2") (pintype "passive"))
    )
    (net (code "29") (name "Net-(D10-A)") (class "Default")
      (node (ref "D10") (pin "1") (pinfunction "A_1") (pintype "passive"))
      (node (ref "R25") (pin "2") (pinfunction "2_2") (pintype "passive"))
    )
    (net (code "30") (name "Net-(D10-K)") (class "Default")
      (node (ref "C27") (pin "2") (pinfunction "2_2") (pintype "passive"))
      (node (ref "D10") (pin "2") (pinfunction "K_2") (pintype "passive"))
      (node (ref "D11") (pin "1") (pinfunction "A_1") (pintype "passive"))
      (node (ref "Q4") (pin "3") (pinfunction "C_3") (pintype "passive"))
      (node (ref "RL4") (pin "2") (pinfunction "9_2") (pintype "passive"))
    )
    (net (code "31") (name "Net-(D12-A)") (class "Default")
      (node (ref "D12") (pin "1") (pinfunction "A_1") (pintype "passive"))
      (node (ref "R29") (pin "2") (pinfunction "2_2") (pintype "passive"))
    )
    (net (code "32") (name "Net-(D12-K)") (class "Default")
      (node (ref "C29") (pin "2") (pinfunction "2_2") (pintype "passive"))
      (node (ref "D12") (pin "2") (pinfunction "K_2") (pintype "passive"))
      (node (ref "D13") (pin "1") (pinfunction "A_1") (pintype "passive"))
      (node (ref "Q5") (pin "3") (pinfunction "C_3") (pintype "passive"))
      (node (ref "RL5") (pin "2") (pinfunction "9_2") (pintype "passive"))
    )
    (net (code "33") (name "Net-(D14-A)") (class "Default")
      (node (ref "D14") (pin "1") (pinfunction "A_1") (pintype "passive"))
      (node (ref "R34") (pin "2") (pinfunction "2_2") (pintype "passive"))
    )
    (net (code "34") (name "Net-(D14-K)") (class "Default")
      (node (ref "C31") (pin "2") (pinfunction "2_2") (pintype "passive"))
      (node (ref "D14") (pin "2") (pinfunction "K_2") (pintype "passive"))
      (node (ref "D15") (pin "1") (pinfunction "A_1") (pintype "passive"))
      (node (ref "Q6") (pin "3") (pinfunction "C_3") (pintype "passive"))
      (node (ref "RL6") (pin "2") (pinfunction "9_2") (pintype "passive"))
    )
    (net (code "35") (name "Net-(D16-A)") (class "Default")
      (node (ref "D16") (pin "1") (pinfunction "A_1") (pintype "passive"))
      (node (ref "R37") (pin "2") (pinfunction "2_2") (pintype "passive"))
    )
    (net (code "36") (name "Net-(D16-K)") (class "Default")
      (node (ref "C33") (pin "2") (pinfunction "2_2") (pintype "passive"))
      (node (ref "D16") (pin "2") (pinfunction "K_2") (pintype "passive"))
      (node (ref "D17") (pin "1") (pinfunction "A_1") (pintype "passive"))
      (node (ref "Q7") (pin "3") (pinfunction "C_3") (pintype "passive"))
      (node (ref "RL7") (pin "2") (pinfunction "9_2") (pintype "passive"))
    )
    (net (code "37") (name "Net-(D18-A)") (class "Default")
      (node (ref "D18") (pin "1") (pinfunction "A_1") (pintype "passive"))
      (node (ref "R40") (pin "2") (pinfunction "2_2") (pintype "passive"))
    )
    (net (code "38") (name "Net-(D18-K)") (class "Default")
      (node (ref "C35") (pin "2") (pinfunction "2_2") (pintype "passive"))
      (node (ref "D18") (pin "2") (pinfunction "K_2") (pintype "passive"))
      (node (ref "D19") (pin "1") (pinfunction "A_1") (pintype "passive"))
      (node (ref "Q8") (pin "3") (pinfunction "C_3") (pintype "passive"))
      (node (ref "RL8") (pin "2") (pinfunction "9_2") (pintype "passive"))
    )
    (net (code "39") (name "Net-(Q1-B)") (class "Default")
      (node (ref "Q1") (pin "2") (pinfunction "B_2") (pintype "passive"))
      (node (ref "R13") (pin "2") (pinfunction "2_2") (pintype "passive"))
      (node (ref "R14") (pin "1") (pinfunction "1_1") (pintype "passive"))
    )
    (net (code "40") (name "Net-(Q2-B)") (class "Default")
      (node (ref "Q2") (pin "2") (pinfunction "B_2") (pintype "passive"))
      (node (ref "R18") (pin "2") (pinfunction "2_2") (pintype "passive"))
      (node (ref "R19") (pin "1") (pinfunction "1_1") (pintype "passive"))
    )
    (net (code "41") (name "Net-(Q3-B)") (class "Default")
      (node (ref "Q3") (pin "2") (pinfunction "B_2") (pintype "passive"))
      (node (ref "R22") (pin "2") (pinfunction "2_2") (pintype "passive"))
      (node (ref "R23") (pin "1") (pinfunction "1_1") (pintype "passive"))
    )
    (net (code "42") (name "Net-(Q4-B)") (class "Default")
      (node (ref "Q4") (pin "2") (pinfunction "B_2") (pintype "passive"))
      (node (ref "R27") (pin "2") (pinfunction "2_2") (pintype "passive"))
      (node (ref "R28") (pin "1") (pinfunction "1_1") (pintype "passive"))
    )
    (net (code "43") (name "Net-(Q5-B)") (class "Default")
      (node (ref "Q5") (pin "2") (pinfunction "B_2") (pintype "passive"))
      (node (ref "R31") (pin "2") (pinfunction "2_2") (pintype "passive"))
      (node (ref "R32") (pin "1") (pinfunction "1_1") (pintype "passive"))
    )
    (net (code "44") (name "Net-(Q6-B)") (class "Default")
      (node (ref "Q6") (pin "2") (pinfunction "B_2") (pintype "passive"))
      (node (ref "R35") (pin "2") (pinfunction "2_2") (pintype "passive"))
      (node (ref "R36") (pin "1") (pinfunction "1_1") (pintype "passive"))
    )
    (net (code "45") (name "Net-(Q7-B)") (class "Default")
      (node (ref "Q7") (pin "2") (pinfunction "B_2") (pintype "passive"))
      (node (ref "R38") (pin "2") (pinfunction "2_2") (pintype "passive"))
      (node (ref "R39") (pin "1") (pinfunction "1_1") (pintype "passive"))
    )
    (net (code "46") (name "Net-(Q8-B)") (class "Default")
      (node (ref "Q8") (pin "2") (pinfunction "B_2") (pintype "passive"))
      (node (ref "R41") (pin "2") (pinfunction "2_2") (pintype "passive"))
      (node (ref "R42") (pin "1") (pinfunction "1_1") (pintype "passive"))
    )
    (net (code "47") (name "Net-(RL1-11)") (class "Default")
      (node (ref "C22") (pin "1") (pinfunction "1_1") (pintype "passive"))
      (node (ref "P2") (pin "2") (pinfunction "2_2") (pintype "passive"))
      (node (ref "RL1") (pin "3") (pinfunction "11_3") (pintype "passive"))
    )
    (net (code "48") (name "Net-(RL2-11)") (class "Default")
      (node (ref "C24") (pin "1") (pinfunction "1_1") (pintype "passive"))
      (node (ref "P2") (pin "3") (pinfunction "3_3") (pintype "passive"))
      (node (ref "RL2") (pin "3") (pinfunction "11_3") (pintype "passive"))
    )
    (net (code "49") (name "Net-(RL3-11)") (class "Default")
      (node (ref "C26") (pin "1") (pinfunction "1_1") (pintype "passive"))
      (node (ref "P2") (pin "4") (pinfunction "4_4") (pintype "passive"))
      (node (ref "RL3") (pin "3") (pinfunction "11_3") (pintype "passive"))
    )
    (net (code "50") (name "Net-(RL4-11)") (class "Default")
      (node (ref "C28") (pin "1") (pinfunction "1_1") (pintype "passive"))
      (node (ref "P2") (pin "5") (pinfunction "5_5") (pintype "passive"))
      (node (ref "RL4") (pin "3") (pinfunction "11_3") (pintype "passive"))
    )
    (net (code "51") (name "Net-(RL5-11)") (class "Default")
      (node (ref "C30") (pin "1") (pinfunction "1_1") (pintype "passive"))
      (node (ref "P2") (pin "7") (pinfunction "7_7") (pintype "passive"))
      (node (ref "RL5") (pin "3") (pinfunction "11_3") (pintype "passive"))
    )
    (net (code "52") (name "Net-(RL6-11)") (class "Default")
      (node (ref "C32") (pin "1") (pinfunction "1_1") (pintype "passive"))
      (node (ref "P2") (pin "8") (pinfunction "8_8") (pintype "passive"))
      (node (ref "RL6") (pin "3") (pinfunction "11_3") (pintype "passive"))
    )
    (net (code "53") (name "Net-(RL7-11)") (class "Default")
      (node (ref "C34") (pin "1") (pinfunction "1_1") (pintype "passive"))
      (node (ref "P2") (pin "9") (pinfunction "9_9") (pintype "passive"))
      (node (ref "RL7") (pin "3") (pinfunction "11_3") (pintype "passive"))
    )
    (net (code "54") (name "Net-(RL8-11)") (class "Default")
      (node (ref "C36") (pin "1") (pinfunction "1_1") (pintype "passive"))
      (node (ref "P2") (pin "10") (pinfunction "10_10") (pintype "passive"))
      (node (ref "RL8") (pin "3") (pinfunction "11_3") (pintype "passive"))
    )
    (net (code "55") (name "Net-(U4-A)") (class "Default")
      (node (ref "R12") (pin "2") (pinfunction "2_2") (pintype "passive"))
      (node (ref "U4") (pin "1") (pinfunction "A_1") (pintype "passive"))
    )
    (net (code "56") (name "Net-(U5-A)") (class "Default")
      (node (ref "R15") (pin "2") (pinfunction "2_2") (pintype "passive"))
      (node (ref "U5") (pin "1") (pinfunction "A_1") (pintype "passive"))
    )
    (net (code "57") (name "Net-(U6-A)") (class "Default")
      (node (ref "R17") (pin "2") (pinfunction "2_2") (pintype "passive"))
      (node (ref "U6") (pin "1") (pinfunction "A_1") (pintype "passive"))
    )
    (net (code "58") (name "Net-(U7-A)") (class "Default")
      (node (ref "R21") (pin "2") (pinfunction "2_2") (pintype "passive"))
      (node (ref "U7") (pin "1") (pinfunction "A_1") (pintype "passive"))
    )
    (net (code "59") (name "Net-(U8-A)") (class "Default")
      (node (ref "R24") (pin "2") (pinfunction "2_2") (pintype "passive"))
      (node (ref "U8") (pin "1") (pinfunction "A_1") (pintype "passive"))
    )
    (net (code "60") (name "Net-(U9-A)") (class "Default")
      (node (ref "R26") (pin "2") (pinfunction "2_2") (pintype "passive"))
      (node (ref "U9") (pin "1") (pinfunction "A_1") (pintype "passive"))
    )
    (net (code "61") (name "Net-(U10-A)") (class "Default")
      (node (ref "R30") (pin "2") (pinfunction "2_2") (pintype "passive"))
      (node (ref "U10") (pin "1") (pinfunction "A_1") (pintype "passive"))
    )
    (net (code "62") (name "Net-(U11-A)") (class "Default")
      (node (ref "R33") (pin "2") (pinfunction "2_2") (pintype "passive"))
      (node (ref "U11") (pin "1") (pinfunction "A_1") (pintype "passive"))
    )
  )
)
